# AK4493-Combi8.net
KiCad netlist of a schematic drawn in EAGLE
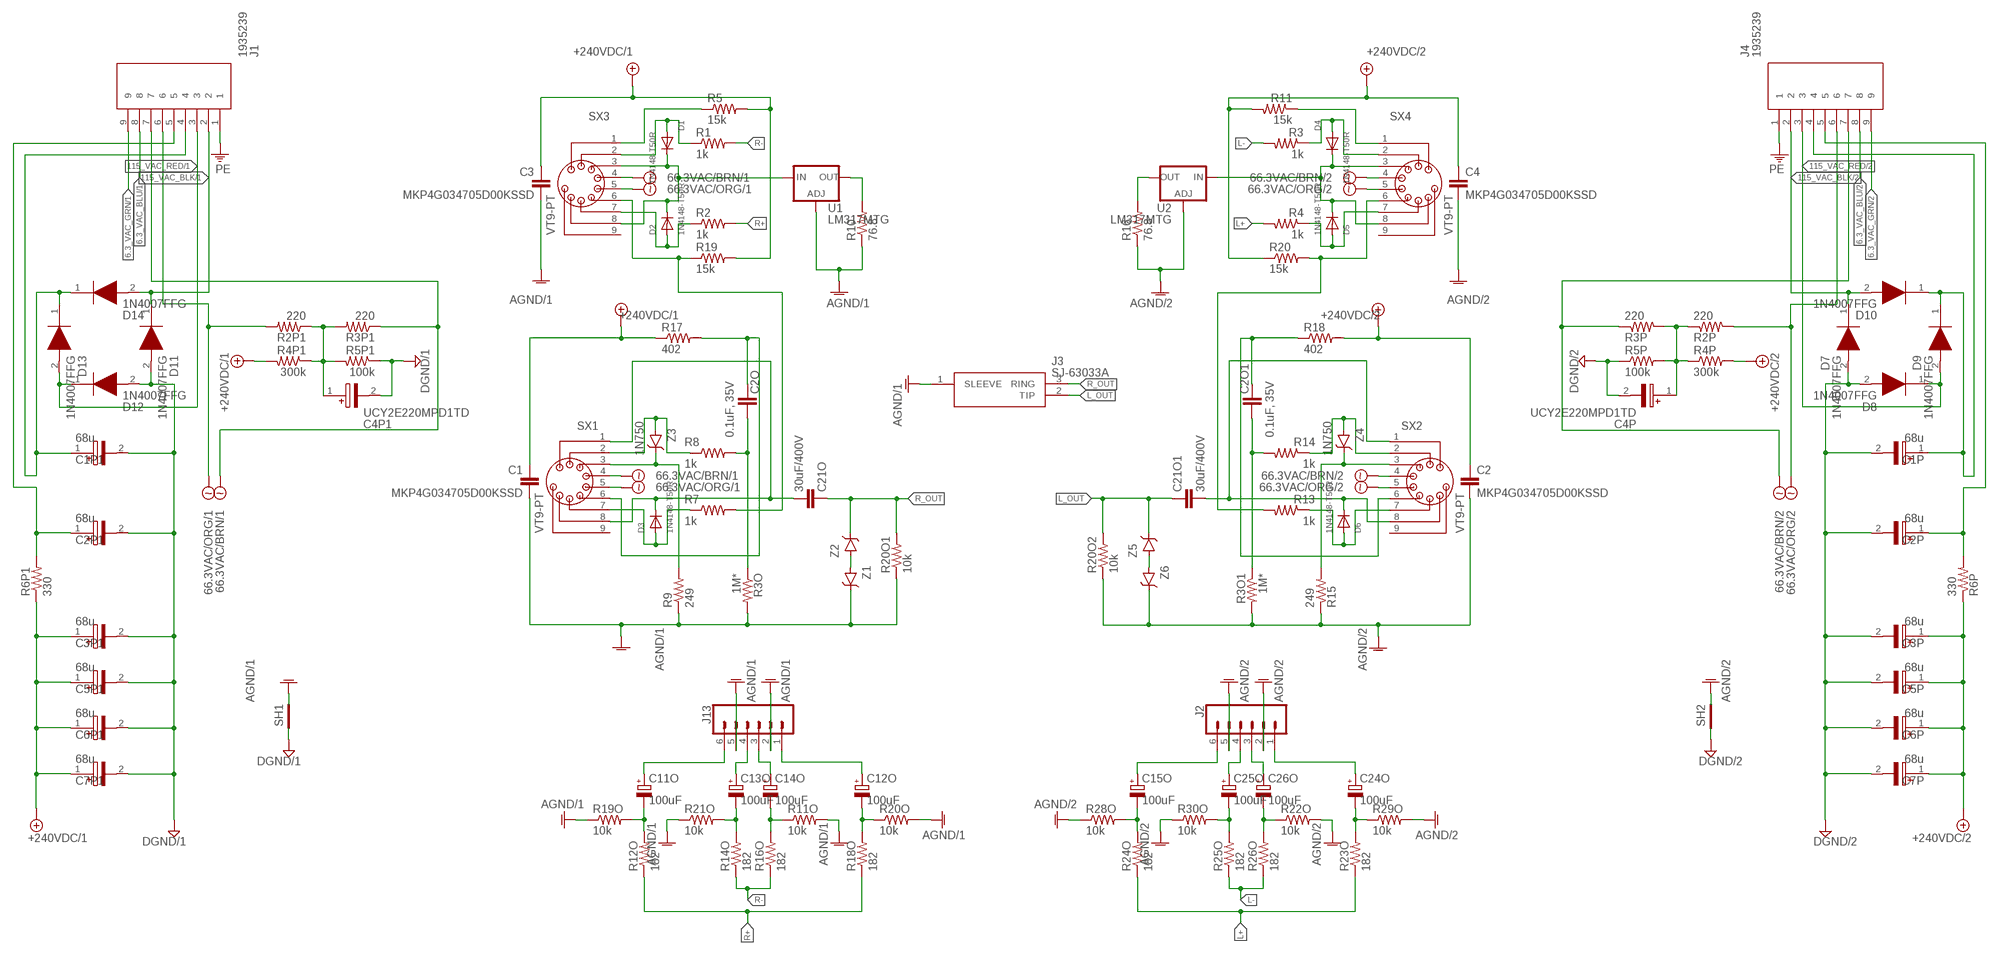
[diagram p0: schematic, sheet 1]

(export (version "E")
  (design (tool "Eeschema 10.0.6"))
  (components
    (comp (ref "C1")
      (value "MKP4G034705D00KSSD")
      (footprint "eagle-import:MKP4G034705D00KSSD")
      (fields (field (name "MOUSER_PART_NUMBER") "505-MKP4G034705DKSSD"))
      (libsource (lib "eagle-import") (part "MKP4G034705D00KSSD"))
    )
    (comp (ref "C1P")
      (value "68u")
      (footprint "eagle-import:CAPPRD750W80D1475H4700")
      (fields (field (name "MANUFACTURER_PART_NUMBER") "500HXW68MEFR14.5X45"))
      (libsource (lib "eagle-import") (part "500HXW68MEFR14.5X45"))
    )
    (comp (ref "C1P1")
      (value "68u")
      (footprint "eagle-import:CAPPRD750W80D1475H4700")
      (fields (field (name "MANUFACTURER_PART_NUMBER") "500HXW68MEFR14.5X45"))
      (libsource (lib "eagle-import") (part "500HXW68MEFR14.5X45"))
    )
    (comp (ref "C2")
      (value "MKP4G034705D00KSSD")
      (footprint "eagle-import:MKP4G034705D00KSSD")
      (fields (field (name "MOUSER_PART_NUMBER") "505-MKP4G034705DKSSD"))
      (libsource (lib "eagle-import") (part "MKP4G034705D00KSSD"))
    )
    (comp (ref "C2O")
      (value "0.1uF, 35V")
      (footprint "eagle-import:MKS4B031002A00JC00")
      (fields
        (field (name "MANUFACTURER_PART_NUMBER") "MKS4B031002A00JC00")
        (field (name "MOUSER_PART_NUMBER") "505-MKS4B0312AJC")
      )
      (libsource (lib "eagle-import") (part "MKS4B031002A00JC00"))
    )
    (comp (ref "C2O1")
      (value "0.1uF, 35V")
      (footprint "eagle-import:MKS4B031002A00JC00")
      (fields
        (field (name "MANUFACTURER_PART_NUMBER") "MKS4B031002A00JC00")
        (field (name "MOUSER_PART_NUMBER") "505-MKS4B0312AJC")
      )
      (libsource (lib "eagle-import") (part "MKS4B031002A00JC00"))
    )
    (comp (ref "C2P")
      (value "68u")
      (footprint "eagle-import:CAPPRD750W80D1475H4700")
      (fields (field (name "MANUFACTURER_PART_NUMBER") "500HXW68MEFR14.5X45"))
      (libsource (lib "eagle-import") (part "500HXW68MEFR14.5X45"))
    )
    (comp (ref "C2P1")
      (value "68u")
      (footprint "eagle-import:CAPPRD750W80D1475H4700")
      (fields (field (name "MANUFACTURER_PART_NUMBER") "500HXW68MEFR14.5X45"))
      (libsource (lib "eagle-import") (part "500HXW68MEFR14.5X45"))
    )
    (comp (ref "C3")
      (value "MKP4G034705D00KSSD")
      (footprint "eagle-import:MKP4G034705D00KSSD")
      (fields (field (name "MOUSER_PART_NUMBER") "505-MKP4G034705DKSSD"))
      (libsource (lib "eagle-import") (part "MKP4G034705D00KSSD"))
    )
    (comp (ref "C3P")
      (value "68u")
      (footprint "eagle-import:CAPPRD750W80D1475H4700")
      (fields (field (name "MANUFACTURER_PART_NUMBER") "500HXW68MEFR14.5X45"))
      (libsource (lib "eagle-import") (part "500HXW68MEFR14.5X45"))
    )
    (comp (ref "C3P1")
      (value "68u")
      (footprint "eagle-import:CAPPRD750W80D1475H4700")
      (fields (field (name "MANUFACTURER_PART_NUMBER") "500HXW68MEFR14.5X45"))
      (libsource (lib "eagle-import") (part "500HXW68MEFR14.5X45"))
    )
    (comp (ref "C4")
      (value "MKP4G034705D00KSSD")
      (footprint "eagle-import:MKP4G034705D00KSSD")
      (fields (field (name "MOUSER_PART_NUMBER") "505-MKP4G034705DKSSD"))
      (libsource (lib "eagle-import") (part "MKP4G034705D00KSSD"))
    )
    (comp (ref "C4P")
      (value "UCY2E220MPD1TD")
      (footprint "eagle-import:CAPPRD500W60D1025H1750")
      (fields (field (name "MOUSER_PART_NUMBER") "647-UCY2E220MPD1TD"))
      (libsource (lib "eagle-import") (part "UCY2E220MPD1TD"))
    )
    (comp (ref "C4P1")
      (value "UCY2E220MPD1TD")
      (footprint "eagle-import:CAPPRD500W60D1025H1750")
      (fields (field (name "MOUSER_PART_NUMBER") "647-UCY2E220MPD1TD"))
      (libsource (lib "eagle-import") (part "UCY2E220MPD1TD"))
    )
    (comp (ref "C5P")
      (value "68u")
      (footprint "eagle-import:CAPPRD750W80D1475H4700")
      (fields (field (name "MANUFACTURER_PART_NUMBER") "500HXW68MEFR14.5X45"))
      (libsource (lib "eagle-import") (part "500HXW68MEFR14.5X45"))
    )
    (comp (ref "C5P1")
      (value "68u")
      (footprint "eagle-import:CAPPRD750W80D1475H4700")
      (fields (field (name "MANUFACTURER_PART_NUMBER") "500HXW68MEFR14.5X45"))
      (libsource (lib "eagle-import") (part "500HXW68MEFR14.5X45"))
    )
    (comp (ref "C6P")
      (value "68u")
      (footprint "eagle-import:CAPPRD750W80D1475H4700")
      (fields (field (name "MANUFACTURER_PART_NUMBER") "500HXW68MEFR14.5X45"))
      (libsource (lib "eagle-import") (part "500HXW68MEFR14.5X45"))
    )
    (comp (ref "C6P1")
      (value "68u")
      (footprint "eagle-import:CAPPRD750W80D1475H4700")
      (fields (field (name "MANUFACTURER_PART_NUMBER") "500HXW68MEFR14.5X45"))
      (libsource (lib "eagle-import") (part "500HXW68MEFR14.5X45"))
    )
    (comp (ref "C7P")
      (value "68u")
      (footprint "eagle-import:CAPPRD750W80D1475H4700")
      (fields (field (name "MANUFACTURER_PART_NUMBER") "500HXW68MEFR14.5X45"))
      (libsource (lib "eagle-import") (part "500HXW68MEFR14.5X45"))
    )
    (comp (ref "C7P1")
      (value "68u")
      (footprint "eagle-import:CAPPRD750W80D1475H4700")
      (fields (field (name "MANUFACTURER_PART_NUMBER") "500HXW68MEFR14.5X45"))
      (libsource (lib "eagle-import") (part "500HXW68MEFR14.5X45"))
    )
    (comp (ref "C11O")
      (value "100uF")
      (footprint "eagle-import:CAPPRD350W60D825H1300")
      (fields
        (field (name "ARROW_PART_NUMBER") "UFW1H101MPD1TD")
        (field (name "MOUSER_PART_NUMBER") "647-UFW1H101MPD1TD")
      )
      (libsource (lib "eagle-import") (part "UFW1H101MPD1TD"))
    )
    (comp (ref "C12O")
      (value "100uF")
      (footprint "eagle-import:CAPPRD350W60D825H1300")
      (fields
        (field (name "ARROW_PART_NUMBER") "UFW1H101MPD1TD")
        (field (name "MOUSER_PART_NUMBER") "647-UFW1H101MPD1TD")
      )
      (libsource (lib "eagle-import") (part "UFW1H101MPD1TD"))
    )
    (comp (ref "C13O")
      (value "100uF")
      (footprint "eagle-import:CAPPRD350W60D825H1300")
      (fields
        (field (name "ARROW_PART_NUMBER") "UFW1H101MPD1TD")
        (field (name "MOUSER_PART_NUMBER") "647-UFW1H101MPD1TD")
      )
      (libsource (lib "eagle-import") (part "UFW1H101MPD1TD"))
    )
    (comp (ref "C14O")
      (value "100uF")
      (footprint "eagle-import:CAPPRD350W60D825H1300")
      (fields
        (field (name "ARROW_PART_NUMBER") "UFW1H101MPD1TD")
        (field (name "MOUSER_PART_NUMBER") "647-UFW1H101MPD1TD")
      )
      (libsource (lib "eagle-import") (part "UFW1H101MPD1TD"))
    )
    (comp (ref "C15O")
      (value "100uF")
      (footprint "eagle-import:CAPPRD350W60D825H1300")
      (fields
        (field (name "ARROW_PART_NUMBER") "UFW1H101MPD1TD")
        (field (name "MOUSER_PART_NUMBER") "647-UFW1H101MPD1TD")
      )
      (libsource (lib "eagle-import") (part "UFW1H101MPD1TD"))
    )
    (comp (ref "C21O")
      (value "30uF/400V")
      (footprint "eagle-import:DCP4G056007GD4KSSD")
      (fields
        (field (name "MANUFACTURER_PART_NUMBER") "DCP4G056007GD4KSSD")
        (field (name "MOUSER_PART_NUMBER") "505-DCP4G056007GD4KS")
      )
      (libsource (lib "eagle-import") (part "DCP4G056007GD4KSSD"))
    )
    (comp (ref "C21O1")
      (value "30uF/400V")
      (footprint "eagle-import:DCP4G056007GD4KSSD")
      (fields
        (field (name "MANUFACTURER_PART_NUMBER") "DCP4G056007GD4KSSD")
        (field (name "MOUSER_PART_NUMBER") "505-DCP4G056007GD4KS")
      )
      (libsource (lib "eagle-import") (part "DCP4G056007GD4KSSD"))
    )
    (comp (ref "C24O")
      (value "100uF")
      (footprint "eagle-import:CAPPRD350W60D825H1300")
      (fields
        (field (name "ARROW_PART_NUMBER") "UFW1H101MPD1TD")
        (field (name "MOUSER_PART_NUMBER") "647-UFW1H101MPD1TD")
      )
      (libsource (lib "eagle-import") (part "UFW1H101MPD1TD"))
    )
    (comp (ref "C25O")
      (value "100uF")
      (footprint "eagle-import:CAPPRD350W60D825H1300")
      (fields
        (field (name "ARROW_PART_NUMBER") "UFW1H101MPD1TD")
        (field (name "MOUSER_PART_NUMBER") "647-UFW1H101MPD1TD")
      )
      (libsource (lib "eagle-import") (part "UFW1H101MPD1TD"))
    )
    (comp (ref "C26O")
      (value "100uF")
      (footprint "eagle-import:CAPPRD350W60D825H1300")
      (fields
        (field (name "ARROW_PART_NUMBER") "UFW1H101MPD1TD")
        (field (name "MOUSER_PART_NUMBER") "647-UFW1H101MPD1TD")
      )
      (libsource (lib "eagle-import") (part "UFW1H101MPD1TD"))
    )
    (comp (ref "D1")
      (value "1N4148-T50R")
      (footprint "eagle-import:DIOAD1068W53L380D172")
      (fields (field (name "MOUSER_PART_NUMBER") "512-1N4148T50R"))
      (libsource (lib "eagle-import") (part "1N4148-T50R"))
    )
    (comp (ref "D2")
      (value "1N4148-T50R")
      (footprint "eagle-import:DIOAD1068W53L380D172")
      (fields (field (name "MOUSER_PART_NUMBER") "512-1N4148T50R"))
      (libsource (lib "eagle-import") (part "1N4148-T50R"))
    )
    (comp (ref "D3")
      (value "1N4148-T50R")
      (footprint "eagle-import:DIOAD1068W53L380D172")
      (fields (field (name "MOUSER_PART_NUMBER") "512-1N4148T50R"))
      (libsource (lib "eagle-import") (part "1N4148-T50R"))
    )
    (comp (ref "D4")
      (value "1N4148-T50R")
      (footprint "eagle-import:DIOAD1068W53L380D172")
      (fields (field (name "MOUSER_PART_NUMBER") "512-1N4148T50R"))
      (libsource (lib "eagle-import") (part "1N4148-T50R"))
    )
    (comp (ref "D5")
      (value "1N4148-T50R")
      (footprint "eagle-import:DIOAD1068W53L380D172")
      (fields (field (name "MOUSER_PART_NUMBER") "512-1N4148T50R"))
      (libsource (lib "eagle-import") (part "1N4148-T50R"))
    )
    (comp (ref "D6")
      (value "1N4148-T50R")
      (footprint "eagle-import:DIOAD1068W53L380D172")
      (fields (field (name "MOUSER_PART_NUMBER") "512-1N4148T50R"))
      (libsource (lib "eagle-import") (part "1N4148-T50R"))
    )
    (comp (ref "D7")
      (value "1N4007FFG")
      (footprint "eagle-import:DIOAD1405W86L465D235")
      (fields (field (name "MOUSER_PART_NUMBER") "863-1N4007FFG"))
      (libsource (lib "eagle-import") (part "1N4007FFG"))
    )
    (comp (ref "D8")
      (value "1N4007FFG")
      (footprint "eagle-import:DIOAD1405W86L465D235")
      (fields (field (name "MOUSER_PART_NUMBER") "863-1N4007FFG"))
      (libsource (lib "eagle-import") (part "1N4007FFG"))
    )
    (comp (ref "D9")
      (value "1N4007FFG")
      (footprint "eagle-import:DIOAD1405W86L465D235")
      (fields (field (name "MOUSER_PART_NUMBER") "863-1N4007FFG"))
      (libsource (lib "eagle-import") (part "1N4007FFG"))
    )
    (comp (ref "D10")
      (value "1N4007FFG")
      (footprint "eagle-import:DIOAD1405W86L465D235")
      (fields (field (name "MOUSER_PART_NUMBER") "863-1N4007FFG"))
      (libsource (lib "eagle-import") (part "1N4007FFG"))
    )
    (comp (ref "D11")
      (value "1N4007FFG")
      (footprint "eagle-import:DIOAD1405W86L465D235")
      (fields (field (name "MOUSER_PART_NUMBER") "863-1N4007FFG"))
      (libsource (lib "eagle-import") (part "1N4007FFG"))
    )
    (comp (ref "D12")
      (value "1N4007FFG")
      (footprint "eagle-import:DIOAD1405W86L465D235")
      (fields (field (name "MOUSER_PART_NUMBER") "863-1N4007FFG"))
      (libsource (lib "eagle-import") (part "1N4007FFG"))
    )
    (comp (ref "D13")
      (value "1N4007FFG")
      (footprint "eagle-import:DIOAD1405W86L465D235")
      (fields (field (name "MOUSER_PART_NUMBER") "863-1N4007FFG"))
      (libsource (lib "eagle-import") (part "1N4007FFG"))
    )
    (comp (ref "D14")
      (value "1N4007FFG")
      (footprint "eagle-import:DIOAD1405W86L465D235")
      (fields (field (name "MOUSER_PART_NUMBER") "863-1N4007FFG"))
      (libsource (lib "eagle-import") (part "1N4007FFG"))
    )
    (comp (ref "J1")
      (value "1935239")
      (footprint "eagle-import:1935239")
      (fields (field (name "MOUSER_PART_NUMBER") "651-1935239"))
      (libsource (lib "eagle-import") (part "1935239"))
    )
    (comp (ref "J2")
      (value "CONN_06SILK_FEMALE_PTH")
      (footprint "eagle-import:1X06")
      (libsource (lib "eagle-import") (part "CONN_06SILK_FEMALE_PTH"))
    )
    (comp (ref "J3")
      (value "SJ-63033A")
      (footprint "eagle-import:SJ63033A")
      (libsource (lib "eagle-import") (part "SJ-63033A"))
    )
    (comp (ref "J4")
      (value "1935239")
      (footprint "eagle-import:1935239")
      (fields (field (name "MOUSER_PART_NUMBER") "651-1935239"))
      (libsource (lib "eagle-import") (part "1935239"))
    )
    (comp (ref "J13")
      (value "CONN_06SILK_FEMALE_PTH")
      (footprint "eagle-import:1X06")
      (libsource (lib "eagle-import") (part "CONN_06SILK_FEMALE_PTH"))
    )
    (comp (ref "R1")
      (value "1k")
      (footprint "eagle-import:0207_10")
      (fields
        (field (name "MANUFACTURER_PART_NUMBER") "LR1F1K0")
        (field (name "MOUSER_PART_NUMBER") "279-LR1F1K0")
      )
      (libsource (lib "eagle-import") (part "LR1F1K0"))
    )
    (comp (ref "R2")
      (value "1k")
      (footprint "eagle-import:0207_10")
      (fields
        (field (name "MANUFACTURER_PART_NUMBER") "LR1F1K0")
        (field (name "MOUSER_PART_NUMBER") "279-LR1F1K0")
      )
      (libsource (lib "eagle-import") (part "LR1F1K0"))
    )
    (comp (ref "R2P")
      (value "220")
      (footprint "eagle-import:0411_15")
      (libsource (lib "eagle-import") (part "R-US_0411/15"))
    )
    (comp (ref "R2P1")
      (value "220")
      (footprint "eagle-import:0411_15")
      (libsource (lib "eagle-import") (part "R-US_0411/15"))
    )
    (comp (ref "R3")
      (value "1k")
      (footprint "eagle-import:0207_10")
      (fields
        (field (name "MANUFACTURER_PART_NUMBER") "LR1F1K0")
        (field (name "MOUSER_PART_NUMBER") "279-LR1F1K0")
      )
      (libsource (lib "eagle-import") (part "LR1F1K0"))
    )
    (comp (ref "R3O")
      (value "1M*")
      (footprint "eagle-import:0207_10")
      (fields
        (field (name "MANUFACTURER_PART_NUMBER") "LR1F1M0")
        (field (name "MOUSER_PART_NUMBER") "279-LR1F1M0")
      )
      (libsource (lib "eagle-import") (part "LR1F1M0"))
    )
    (comp (ref "R3O1")
      (value "1M*")
      (footprint "eagle-import:0207_10")
      (fields
        (field (name "MANUFACTURER_PART_NUMBER") "LR1F1M0")
        (field (name "MOUSER_PART_NUMBER") "279-LR1F1M0")
      )
      (libsource (lib "eagle-import") (part "LR1F1M0"))
    )
    (comp (ref "R3P")
      (value "220")
      (footprint "eagle-import:0411_15")
      (libsource (lib "eagle-import") (part "R-US_0411/15"))
    )
    (comp (ref "R3P1")
      (value "220")
      (footprint "eagle-import:0411_15")
      (libsource (lib "eagle-import") (part "R-US_0411/15"))
    )
    (comp (ref "R4")
      (value "1k")
      (footprint "eagle-import:0207_10")
      (fields
        (field (name "MANUFACTURER_PART_NUMBER") "LR1F1K0")
        (field (name "MOUSER_PART_NUMBER") "279-LR1F1K0")
      )
      (libsource (lib "eagle-import") (part "LR1F1K0"))
    )
    (comp (ref "R4P")
      (value "300k")
      (footprint "eagle-import:0411_15")
      (libsource (lib "eagle-import") (part "R-US_0411/15"))
    )
    (comp (ref "R4P1")
      (value "300k")
      (footprint "eagle-import:0411_15")
      (libsource (lib "eagle-import") (part "R-US_0411/15"))
    )
    (comp (ref "R5")
      (value "15k")
      (footprint "eagle-import:0411_15")
      (fields
        (field (name "MANUFACTURER_PART_NUMBER") "CPF215K000FKE14")
        (field (name "MOUSER_PART_NUMBER") "71-CPF2-F-15K-E3")
      )
      (libsource (lib "eagle-import") (part "CPF215K000FKE14"))
    )
    (comp (ref "R5P")
      (value "100k")
      (footprint "eagle-import:0411_15")
      (libsource (lib "eagle-import") (part "R-US_0411/15"))
    )
    (comp (ref "R5P1")
      (value "100k")
      (footprint "eagle-import:0411_15")
      (libsource (lib "eagle-import") (part "R-US_0411/15"))
    )
    (comp (ref "R6P")
      (value "330")
      (footprint "eagle-import:0411_15")
      (libsource (lib "eagle-import") (part "R-US_0411/15"))
    )
    (comp (ref "R6P1")
      (value "330")
      (footprint "eagle-import:0411_15")
      (libsource (lib "eagle-import") (part "R-US_0411/15"))
    )
    (comp (ref "R7")
      (value "1k")
      (footprint "eagle-import:0207_10")
      (fields
        (field (name "MANUFACTURER_PART_NUMBER") "LR1F1K0")
        (field (name "MOUSER_PART_NUMBER") "279-LR1F1K0")
      )
      (libsource (lib "eagle-import") (part "LR1F1K0"))
    )
    (comp (ref "R8")
      (value "1k")
      (footprint "eagle-import:0207_10")
      (fields
        (field (name "MANUFACTURER_PART_NUMBER") "LR1F1K0")
        (field (name "MOUSER_PART_NUMBER") "279-LR1F1K0")
      )
      (libsource (lib "eagle-import") (part "LR1F1K0"))
    )
    (comp (ref "R9")
      (value "249")
      (footprint "eagle-import:0207_10")
      (fields (field (name "MANUFACTURER_PART_NUMBER") "MBB02070C2490FRP00"))
      (libsource (lib "eagle-import") (part "MBB02070C2490FRP00"))
    )
    (comp (ref "R10")
      (value "76.8")
      (footprint "eagle-import:0207_10")
      (fields (field (name "MANUFACTURER_PART_NUMBER") "YR1B76R8CC"))
      (libsource (lib "eagle-import") (part "YR1B76R8CC"))
    )
    (comp (ref "R11")
      (value "15k")
      (footprint "eagle-import:0411_15")
      (fields
        (field (name "MANUFACTURER_PART_NUMBER") "CPF215K000FKE14")
        (field (name "MOUSER_PART_NUMBER") "71-CPF2-F-15K-E3")
      )
      (libsource (lib "eagle-import") (part "CPF215K000FKE14"))
    )
    (comp (ref "R11O")
      (value "10k")
      (footprint "eagle-import:0207_10")
      (fields
        (field (name "MANUFACTURER_PART_NUMBER") "LR1F10K")
        (field (name "MOUSER_PART_NUMBER") "279-LR1F10K")
      )
      (libsource (lib "eagle-import") (part "LR1F10K"))
    )
    (comp (ref "R12O")
      (value "182")
      (footprint "eagle-import:0207_10")
      (fields
        (field (name "MANUFACTURER") "Yageo")
        (field (name "MANUFACTURER_PART_NUMBER") "MF0207FTE52-182R")
        (field (name "MOUSER_PART_NUMBER") "603-MF0207FTE52-182R")
      )
      (libsource (lib "eagle-import") (part "MF0207FTE52-182R"))
    )
    (comp (ref "R13")
      (value "1k")
      (footprint "eagle-import:0207_10")
      (fields
        (field (name "MANUFACTURER_PART_NUMBER") "LR1F1K0")
        (field (name "MOUSER_PART_NUMBER") "279-LR1F1K0")
      )
      (libsource (lib "eagle-import") (part "LR1F1K0"))
    )
    (comp (ref "R14")
      (value "1k")
      (footprint "eagle-import:0207_10")
      (fields
        (field (name "MANUFACTURER_PART_NUMBER") "LR1F1K0")
        (field (name "MOUSER_PART_NUMBER") "279-LR1F1K0")
      )
      (libsource (lib "eagle-import") (part "LR1F1K0"))
    )
    (comp (ref "R14O")
      (value "182")
      (footprint "eagle-import:0207_10")
      (fields
        (field (name "MANUFACTURER") "Yageo")
        (field (name "MANUFACTURER_PART_NUMBER") "MF0207FTE52-182R")
        (field (name "MOUSER_PART_NUMBER") "603-MF0207FTE52-182R")
      )
      (libsource (lib "eagle-import") (part "MF0207FTE52-182R"))
    )
    (comp (ref "R15")
      (value "249")
      (footprint "eagle-import:0207_10")
      (fields (field (name "MANUFACTURER_PART_NUMBER") "MBB02070C2490FRP00"))
      (libsource (lib "eagle-import") (part "MBB02070C2490FRP00"))
    )
    (comp (ref "R16")
      (value "76.8")
      (footprint "eagle-import:0207_10")
      (fields (field (name "MANUFACTURER_PART_NUMBER") "YR1B76R8CC"))
      (libsource (lib "eagle-import") (part "YR1B76R8CC"))
    )
    (comp (ref "R16O")
      (value "182")
      (footprint "eagle-import:0207_10")
      (fields
        (field (name "MANUFACTURER") "Yageo")
        (field (name "MANUFACTURER_PART_NUMBER") "MF0207FTE52-182R")
        (field (name "MOUSER_PART_NUMBER") "603-MF0207FTE52-182R")
      )
      (libsource (lib "eagle-import") (part "MF0207FTE52-182R"))
    )
    (comp (ref "R17")
      (value "402")
      (footprint "eagle-import:0617_22")
      (fields (field (name "MANUFACTURER_PART_NUMBER") "RWR80S4020FRB12"))
      (libsource (lib "eagle-import") (part "RWR80S4020FRB12"))
    )
    (comp (ref "R18")
      (value "402")
      (footprint "eagle-import:0617_22")
      (fields (field (name "MANUFACTURER_PART_NUMBER") "RWR80S4020FRB12"))
      (libsource (lib "eagle-import") (part "RWR80S4020FRB12"))
    )
    (comp (ref "R18O")
      (value "182")
      (footprint "eagle-import:0207_10")
      (fields
        (field (name "MANUFACTURER") "Yageo")
        (field (name "MANUFACTURER_PART_NUMBER") "MF0207FTE52-182R")
        (field (name "MOUSER_PART_NUMBER") "603-MF0207FTE52-182R")
      )
      (libsource (lib "eagle-import") (part "MF0207FTE52-182R"))
    )
    (comp (ref "R19")
      (value "15k")
      (footprint "eagle-import:0411_15")
      (fields
        (field (name "MANUFACTURER_PART_NUMBER") "CPF215K000FKE14")
        (field (name "MOUSER_PART_NUMBER") "71-CPF2-F-15K-E3")
      )
      (libsource (lib "eagle-import") (part "CPF215K000FKE14"))
    )
    (comp (ref "R19O")
      (value "10k")
      (footprint "eagle-import:0207_10")
      (fields
        (field (name "MANUFACTURER_PART_NUMBER") "LR1F10K")
        (field (name "MOUSER_PART_NUMBER") "279-LR1F10K")
      )
      (libsource (lib "eagle-import") (part "LR1F10K"))
    )
    (comp (ref "R20")
      (value "15k")
      (footprint "eagle-import:0411_15")
      (fields
        (field (name "MANUFACTURER_PART_NUMBER") "CPF215K000FKE14")
        (field (name "MOUSER_PART_NUMBER") "71-CPF2-F-15K-E3")
      )
      (libsource (lib "eagle-import") (part "CPF215K000FKE14"))
    )
    (comp (ref "R20O")
      (value "10k")
      (footprint "eagle-import:0207_10")
      (fields
        (field (name "MANUFACTURER_PART_NUMBER") "LR1F10K")
        (field (name "MOUSER_PART_NUMBER") "279-LR1F10K")
      )
      (libsource (lib "eagle-import") (part "LR1F10K"))
    )
    (comp (ref "R20O1")
      (value "10k")
      (footprint "eagle-import:0207_10")
      (fields
        (field (name "MANUFACTURER_PART_NUMBER") "LR1F10K")
        (field (name "MOUSER_PART_NUMBER") "279-LR1F10K")
      )
      (libsource (lib "eagle-import") (part "LR1F10K"))
    )
    (comp (ref "R20O2")
      (value "10k")
      (footprint "eagle-import:0207_10")
      (fields
        (field (name "MANUFACTURER_PART_NUMBER") "LR1F10K")
        (field (name "MOUSER_PART_NUMBER") "279-LR1F10K")
      )
      (libsource (lib "eagle-import") (part "LR1F10K"))
    )
    (comp (ref "R21O")
      (value "10k")
      (footprint "eagle-import:0207_10")
      (fields
        (field (name "MANUFACTURER_PART_NUMBER") "LR1F10K")
        (field (name "MOUSER_PART_NUMBER") "279-LR1F10K")
      )
      (libsource (lib "eagle-import") (part "LR1F10K"))
    )
    (comp (ref "R22O")
      (value "10k")
      (footprint "eagle-import:0207_10")
      (fields
        (field (name "MANUFACTURER_PART_NUMBER") "LR1F10K")
        (field (name "MOUSER_PART_NUMBER") "279-LR1F10K")
      )
      (libsource (lib "eagle-import") (part "LR1F10K"))
    )
    (comp (ref "R23O")
      (value "182")
      (footprint "eagle-import:0207_10")
      (fields
        (field (name "MANUFACTURER") "Yageo")
        (field (name "MANUFACTURER_PART_NUMBER") "MF0207FTE52-182R")
        (field (name "MOUSER_PART_NUMBER") "603-MF0207FTE52-182R")
      )
      (libsource (lib "eagle-import") (part "MF0207FTE52-182R"))
    )
    (comp (ref "R24O")
      (value "182")
      (footprint "eagle-import:0207_10")
      (fields
        (field (name "MANUFACTURER") "Yageo")
        (field (name "MANUFACTURER_PART_NUMBER") "MF0207FTE52-182R")
        (field (name "MOUSER_PART_NUMBER") "603-MF0207FTE52-182R")
      )
      (libsource (lib "eagle-import") (part "MF0207FTE52-182R"))
    )
    (comp (ref "R25O")
      (value "182")
      (footprint "eagle-import:0207_10")
      (fields
        (field (name "MANUFACTURER") "Yageo")
        (field (name "MANUFACTURER_PART_NUMBER") "MF0207FTE52-182R")
        (field (name "MOUSER_PART_NUMBER") "603-MF0207FTE52-182R")
      )
      (libsource (lib "eagle-import") (part "MF0207FTE52-182R"))
    )
    (comp (ref "R26O")
      (value "182")
      (footprint "eagle-import:0207_10")
      (fields
        (field (name "MANUFACTURER") "Yageo")
        (field (name "MANUFACTURER_PART_NUMBER") "MF0207FTE52-182R")
        (field (name "MOUSER_PART_NUMBER") "603-MF0207FTE52-182R")
      )
      (libsource (lib "eagle-import") (part "MF0207FTE52-182R"))
    )
    (comp (ref "R28O")
      (value "10k")
      (footprint "eagle-import:0207_10")
      (fields
        (field (name "MANUFACTURER_PART_NUMBER") "LR1F10K")
        (field (name "MOUSER_PART_NUMBER") "279-LR1F10K")
      )
      (libsource (lib "eagle-import") (part "LR1F10K"))
    )
    (comp (ref "R29O")
      (value "10k")
      (footprint "eagle-import:0207_10")
      (fields
        (field (name "MANUFACTURER_PART_NUMBER") "LR1F10K")
        (field (name "MOUSER_PART_NUMBER") "279-LR1F10K")
      )
      (libsource (lib "eagle-import") (part "LR1F10K"))
    )
    (comp (ref "R30O")
      (value "10k")
      (footprint "eagle-import:0207_10")
      (fields
        (field (name "MANUFACTURER_PART_NUMBER") "LR1F10K")
        (field (name "MOUSER_PART_NUMBER") "279-LR1F10K")
      )
      (libsource (lib "eagle-import") (part "LR1F10K"))
    )
    (comp (ref "SH1")
      (value "SHORTA5")
      (footprint "eagle-import:SHORT_ALL-50")
      (libsource (lib "eagle-import") (part "SHORTA5"))
    )
    (comp (ref "SH2")
      (value "SHORTA5")
      (footprint "eagle-import:SHORT_ALL-50")
      (libsource (lib "eagle-import") (part "SHORTA5"))
    )
    (comp (ref "SX1")
      (value "VT9-PT")
      (footprint "eagle-import:VT9-PT")
      (libsource (lib "eagle-import") (part "VT9-PT"))
    )
    (comp (ref "SX2")
      (value "VT9-PT")
      (footprint "eagle-import:VT9-PT")
      (libsource (lib "eagle-import") (part "VT9-PT"))
    )
    (comp (ref "SX3")
      (value "VT9-PT")
      (footprint "eagle-import:VT9-PT")
      (libsource (lib "eagle-import") (part "VT9-PT"))
    )
    (comp (ref "SX4")
      (value "VT9-PT")
      (footprint "eagle-import:VT9-PT")
      (libsource (lib "eagle-import") (part "VT9-PT"))
    )
    (comp (ref "U1")
      (value "LM317MTG")
      (footprint "eagle-import:TO254P482X997X2018-3P")
      (fields (field (name "MOUSER_PART_NUMBER") "863-LM317MTG"))
      (libsource (lib "eagle-import") (part "LM317MTG"))
    )
    (comp (ref "U2")
      (value "LM317MTG")
      (footprint "eagle-import:TO254P482X997X2018-3P")
      (fields (field (name "MOUSER_PART_NUMBER") "863-LM317MTG"))
      (libsource (lib "eagle-import") (part "LM317MTG"))
    )
    (comp (ref "Z1")
      (value "BZX79-C16,113")
      (footprint "eagle-import:DIOAD1165W56L425D185")
      (libsource (lib "eagle-import") (part "BZX79-C16,113"))
    )
    (comp (ref "Z2")
      (value "BZX79-C16,113")
      (footprint "eagle-import:DIOAD1165W56L425D185")
      (libsource (lib "eagle-import") (part "BZX79-C16,113"))
    )
    (comp (ref "Z3")
      (value "1N750")
      (footprint "eagle-import:DIOAD1256W56L444D203")
      (fields (field (name "MOUSER_PART_NUMBER") "494-1N750(DO-35)"))
      (libsource (lib "eagle-import") (part "1N750"))
    )
    (comp (ref "Z4")
      (value "1N750")
      (footprint "eagle-import:DIOAD1256W56L444D203")
      (fields (field (name "MOUSER_PART_NUMBER") "494-1N750(DO-35)"))
      (libsource (lib "eagle-import") (part "1N750"))
    )
    (comp (ref "Z5")
      (value "BZX79-C16,113")
      (footprint "eagle-import:DIOAD1165W56L425D185")
      (libsource (lib "eagle-import") (part "BZX79-C16,113"))
    )
    (comp (ref "Z6")
      (value "BZX79-C16,113")
      (footprint "eagle-import:DIOAD1165W56L425D185")
      (libsource (lib "eagle-import") (part "BZX79-C16,113"))
    )
  )
  (nets
    (net (code "1") (name "+240VDC{slash}1") (class "Default")
      (node (ref "C1") (pin "1") (pinfunction "1_1") (pintype "passive"))
      (node (ref "C3") (pin "1") (pinfunction "1_1") (pintype "passive"))
      (node (ref "C3P1") (pin "1") (pinfunction "+_1") (pintype "bidirectional"))
      (node (ref "C5P1") (pin "1") (pinfunction "+_1") (pintype "bidirectional"))
      (node (ref "C6P1") (pin "1") (pinfunction "+_1") (pintype "bidirectional"))
      (node (ref "C7P1") (pin "1") (pinfunction "+_1") (pintype "bidirectional"))
      (node (ref "R17") (pin "1") (pinfunction "1_1") (pintype "passive"))
      (node (ref "R19") (pin "2") (pinfunction "2_2") (pintype "passive"))
      (node (ref "R4P1") (pin "2") (pinfunction "2_2") (pintype "passive"))
      (node (ref "R5") (pin "2") (pinfunction "2_2") (pintype "passive"))
      (node (ref "R6P1") (pin "1") (pinfunction "1_1") (pintype "passive"))
    )
    (net (code "2") (name "+240VDC{slash}2") (class "Default")
      (node (ref "C2") (pin "1") (pinfunction "1_1") (pintype "passive"))
      (node (ref "C3P") (pin "1") (pinfunction "+_1") (pintype "bidirectional"))
      (node (ref "C4") (pin "1") (pinfunction "1_1") (pintype "passive"))
      (node (ref "C5P") (pin "1") (pinfunction "+_1") (pintype "bidirectional"))
      (node (ref "C6P") (pin "1") (pinfunction "+_1") (pintype "bidirectional"))
      (node (ref "C7P") (pin "1") (pinfunction "+_1") (pintype "bidirectional"))
      (node (ref "R11") (pin "2") (pinfunction "2_2") (pintype "passive"))
      (node (ref "R18") (pin "2") (pinfunction "2_2") (pintype "passive"))
      (node (ref "R20") (pin "1") (pinfunction "1_1") (pintype "passive"))
      (node (ref "R4P") (pin "2") (pinfunction "2_2") (pintype "passive"))
      (node (ref "R6P") (pin "1") (pinfunction "1_1") (pintype "passive"))
    )
    (net (code "3") (name "6.3_VAC_BLU{slash}1") (class "Default")
      (node (ref "J1") (pin "8") (pinfunction "8_8") (pintype "bidirectional"))
    )
    (net (code "4") (name "6.3_VAC_BLU{slash}2") (class "Default")
      (node (ref "J4") (pin "8") (pinfunction "8_8") (pintype "bidirectional"))
    )
    (net (code "5") (name "6.3_VAC_GRN{slash}1") (class "Default")
      (node (ref "J1") (pin "9") (pinfunction "9_9") (pintype "bidirectional"))
    )
    (net (code "6") (name "6.3_VAC_GRN{slash}2") (class "Default")
      (node (ref "J4") (pin "9") (pinfunction "9_9") (pintype "bidirectional"))
    )
    (net (code "7") (name "66.3VAC{slash}BRN{slash}1") (class "Default")
      (node (ref "J1") (pin "7") (pinfunction "7_7") (pintype "bidirectional"))
      (node (ref "R3P1") (pin "1") (pinfunction "1_1") (pintype "passive"))
      (node (ref "SX1") (pin "4") (pinfunction "4_4") (pintype "passive"))
      (node (ref "SX3") (pin "4") (pinfunction "4_4") (pintype "passive"))
    )
    (net (code "8") (name "66.3VAC{slash}BRN{slash}2") (class "Default")
      (node (ref "J4") (pin "7") (pinfunction "7_7") (pintype "bidirectional"))
      (node (ref "R3P") (pin "1") (pinfunction "1_1") (pintype "passive"))
      (node (ref "SX2") (pin "4") (pinfunction "4_4") (pintype "passive"))
      (node (ref "SX4") (pin "4") (pinfunction "4_4") (pintype "passive"))
    )
    (net (code "9") (name "66.3VAC{slash}ORG{slash}1") (class "Default")
      (node (ref "J1") (pin "6") (pinfunction "6_6") (pintype "bidirectional"))
      (node (ref "R2P1") (pin "2") (pinfunction "2_2") (pintype "passive"))
      (node (ref "SX1") (pin "5") (pinfunction "5_5") (pintype "passive"))
      (node (ref "SX3") (pin "5") (pinfunction "5_5") (pintype "passive"))
    )
    (net (code "10") (name "66.3VAC{slash}ORG{slash}2") (class "Default")
      (node (ref "J4") (pin "6") (pinfunction "6_6") (pintype "bidirectional"))
      (node (ref "R2P") (pin "2") (pinfunction "2_2") (pintype "passive"))
      (node (ref "SX2") (pin "5") (pinfunction "5_5") (pintype "passive"))
      (node (ref "SX4") (pin "5") (pinfunction "5_5") (pintype "passive"))
    )
    (net (code "11") (name "115_VAC_BLK{slash}1") (class "Default")
      (node (ref "D11") (pin "1") (pinfunction "K_1") (pintype "bidirectional"))
      (node (ref "D14") (pin "2") (pinfunction "A_2") (pintype "bidirectional"))
      (node (ref "J1") (pin "2") (pinfunction "2_2") (pintype "bidirectional"))
    )
    (net (code "12") (name "115_VAC_BLK{slash}2") (class "Default")
      (node (ref "D10") (pin "2") (pinfunction "A_2") (pintype "bidirectional"))
      (node (ref "D7") (pin "1") (pinfunction "K_1") (pintype "bidirectional"))
      (node (ref "J4") (pin "2") (pinfunction "2_2") (pintype "bidirectional"))
    )
    (net (code "13") (name "115_VAC_RED{slash}1") (class "Default")
      (node (ref "D12") (pin "1") (pinfunction "K_1") (pintype "bidirectional"))
      (node (ref "D13") (pin "2") (pinfunction "A_2") (pintype "bidirectional"))
      (node (ref "J1") (pin "3") (pinfunction "3_3") (pintype "bidirectional"))
    )
    (net (code "14") (name "115_VAC_RED{slash}2") (class "Default")
      (node (ref "D8") (pin "1") (pinfunction "K_1") (pintype "bidirectional"))
      (node (ref "D9") (pin "2") (pinfunction "A_2") (pintype "bidirectional"))
      (node (ref "J4") (pin "3") (pinfunction "3_3") (pintype "bidirectional"))
    )
    (net (code "15") (name "AGND{slash}1") (class "Default")
      (node (ref "C1") (pin "2") (pinfunction "2_2") (pintype "passive"))
      (node (ref "C3") (pin "2") (pinfunction "2_2") (pintype "passive"))
      (node (ref "J13") (pin "2") (pinfunction "2_2") (pintype "passive"))
      (node (ref "J13") (pin "5") (pinfunction "5_5") (pintype "passive"))
      (node (ref "J3") (pin "1") (pinfunction "SLEEVE_1") (pintype "bidirectional"))
      (node (ref "R10") (pin "1") (pinfunction "1_1") (pintype "passive"))
      (node (ref "R11O") (pin "2") (pinfunction "2_2") (pintype "passive"))
      (node (ref "R19O") (pin "1") (pinfunction "1_1") (pintype "passive"))
      (node (ref "R20O") (pin "2") (pinfunction "2_2") (pintype "passive"))
      (node (ref "R20O1") (pin "1") (pinfunction "1_1") (pintype "passive"))
      (node (ref "R21O") (pin "1") (pinfunction "1_1") (pintype "passive"))
      (node (ref "R3O") (pin "2") (pinfunction "2_2") (pintype "passive"))
      (node (ref "R9") (pin "1") (pinfunction "1_1") (pintype "passive"))
      (node (ref "SH1") (pin "2") (pinfunction "P$2_2") (pintype "bidirectional"))
      (node (ref "U1") (pin "1") (pinfunction "ADJ_1") (pintype "input"))
      (node (ref "Z1") (pin "1") (pinfunction "C_1") (pintype "passive"))
    )
    (net (code "16") (name "AGND{slash}2") (class "Default")
      (node (ref "C2") (pin "2") (pinfunction "2_2") (pintype "passive"))
      (node (ref "C4") (pin "2") (pinfunction "2_2") (pintype "passive"))
      (node (ref "J2") (pin "2") (pinfunction "2_2") (pintype "passive"))
      (node (ref "J2") (pin "5") (pinfunction "5_5") (pintype "passive"))
      (node (ref "R15") (pin "1") (pinfunction "1_1") (pintype "passive"))
      (node (ref "R16") (pin "1") (pinfunction "1_1") (pintype "passive"))
      (node (ref "R20O2") (pin "1") (pinfunction "1_1") (pintype "passive"))
      (node (ref "R22O") (pin "2") (pinfunction "2_2") (pintype "passive"))
      (node (ref "R28O") (pin "1") (pinfunction "1_1") (pintype "passive"))
      (node (ref "R29O") (pin "2") (pinfunction "2_2") (pintype "passive"))
      (node (ref "R30O") (pin "1") (pinfunction "1_1") (pintype "passive"))
      (node (ref "R3O1") (pin "2") (pinfunction "2_2") (pintype "passive"))
      (node (ref "SH2") (pin "2") (pinfunction "P$2_2") (pintype "bidirectional"))
      (node (ref "U2") (pin "1") (pinfunction "ADJ_1") (pintype "input"))
      (node (ref "Z6") (pin "1") (pinfunction "C_1") (pintype "passive"))
    )
    (net (code "17") (name "DGND{slash}1") (class "Default")
      (node (ref "C1P1") (pin "2") (pinfunction "-_2") (pintype "bidirectional"))
      (node (ref "C2P1") (pin "2") (pinfunction "-_2") (pintype "bidirectional"))
      (node (ref "C3P1") (pin "2") (pinfunction "-_2") (pintype "bidirectional"))
      (node (ref "C4P1") (pin "2") (pinfunction "-_2") (pintype "bidirectional"))
      (node (ref "C5P1") (pin "2") (pinfunction "-_2") (pintype "bidirectional"))
      (node (ref "C6P1") (pin "2") (pinfunction "-_2") (pintype "bidirectional"))
      (node (ref "C7P1") (pin "2") (pinfunction "-_2") (pintype "bidirectional"))
      (node (ref "D11") (pin "2") (pinfunction "A_2") (pintype "bidirectional"))
      (node (ref "D12") (pin "2") (pinfunction "A_2") (pintype "bidirectional"))
      (node (ref "R5P1") (pin "1") (pinfunction "1_1") (pintype "passive"))
      (node (ref "SH1") (pin "1") (pinfunction "P$1_1") (pintype "bidirectional"))
    )
    (net (code "18") (name "DGND{slash}2") (class "Default")
      (node (ref "C1P") (pin "2") (pinfunction "-_2") (pintype "bidirectional"))
      (node (ref "C2P") (pin "2") (pinfunction "-_2") (pintype "bidirectional"))
      (node (ref "C3P") (pin "2") (pinfunction "-_2") (pintype "bidirectional"))
      (node (ref "C4P") (pin "2") (pinfunction "-_2") (pintype "bidirectional"))
      (node (ref "C5P") (pin "2") (pinfunction "-_2") (pintype "bidirectional"))
      (node (ref "C6P") (pin "2") (pinfunction "-_2") (pintype "bidirectional"))
      (node (ref "C7P") (pin "2") (pinfunction "-_2") (pintype "bidirectional"))
      (node (ref "D7") (pin "2") (pinfunction "A_2") (pintype "bidirectional"))
      (node (ref "D8") (pin "2") (pinfunction "A_2") (pintype "bidirectional"))
      (node (ref "R5P") (pin "1") (pinfunction "1_1") (pintype "passive"))
      (node (ref "SH2") (pin "1") (pinfunction "P$1_1") (pintype "bidirectional"))
    )
    (net (code "19") (name "L+") (class "Default")
      (node (ref "R23O") (pin "1") (pinfunction "1_1") (pintype "passive"))
      (node (ref "R24O") (pin "1") (pinfunction "1_1") (pintype "passive"))
      (node (ref "R4") (pin "2") (pinfunction "2_2") (pintype "passive"))
    )
    (net (code "20") (name "L-") (class "Default")
      (node (ref "R25O") (pin "1") (pinfunction "1_1") (pintype "passive"))
      (node (ref "R26O") (pin "1") (pinfunction "1_1") (pintype "passive"))
      (node (ref "R3") (pin "2") (pinfunction "2_2") (pintype "passive"))
    )
    (net (code "21") (name "L_OUT") (class "Default")
      (node (ref "C21O1") (pin "1") (pinfunction "1_1") (pintype "passive"))
      (node (ref "C21O1") (pin "4") (pinfunction "1_4") (pintype "passive"))
      (node (ref "J3") (pin "2") (pinfunction "TIP_2") (pintype "bidirectional"))
      (node (ref "R20O2") (pin "2") (pinfunction "2_2") (pintype "passive"))
      (node (ref "Z5") (pin "1") (pinfunction "C_1") (pintype "passive"))
    )
    (net (code "22") (name "Net-(C1P-+)") (class "Default")
      (node (ref "C1P") (pin "1") (pinfunction "+_1") (pintype "bidirectional"))
      (node (ref "D10") (pin "1") (pinfunction "K_1") (pintype "bidirectional"))
      (node (ref "D9") (pin "1") (pinfunction "K_1") (pintype "bidirectional"))
      (node (ref "J4") (pin "4") (pinfunction "4_4") (pintype "bidirectional"))
    )
    (net (code "23") (name "Net-(C1P1-+)") (class "Default")
      (node (ref "C1P1") (pin "1") (pinfunction "+_1") (pintype "bidirectional"))
      (node (ref "D13") (pin "1") (pinfunction "K_1") (pintype "bidirectional"))
      (node (ref "D14") (pin "1") (pinfunction "K_1") (pintype "bidirectional"))
      (node (ref "J1") (pin "4") (pinfunction "4_4") (pintype "bidirectional"))
    )
    (net (code "24") (name "Net-(C2O-Pad1)") (class "Default")
      (node (ref "C2O") (pin "1") (pinfunction "1_1") (pintype "passive"))
      (node (ref "R17") (pin "2") (pinfunction "2_2") (pintype "passive"))
      (node (ref "SX1") (pin "6") (pinfunction "6_6") (pintype "passive"))
    )
    (net (code "25") (name "Net-(C2O-Pad2)") (class "Default")
      (node (ref "C2O") (pin "2") (pinfunction "2_2") (pintype "passive"))
      (node (ref "R3O") (pin "1") (pinfunction "1_1") (pintype "passive"))
      (node (ref "R8") (pin "2") (pinfunction "2_2") (pintype "passive"))
    )
    (net (code "26") (name "Net-(C2O1-Pad1)") (class "Default")
      (node (ref "C2O1") (pin "1") (pinfunction "1_1") (pintype "passive"))
      (node (ref "R18") (pin "1") (pinfunction "1_1") (pintype "passive"))
      (node (ref "SX2") (pin "6") (pinfunction "6_6") (pintype "passive"))
    )
    (net (code "27") (name "Net-(C2O1-Pad2)") (class "Default")
      (node (ref "C2O1") (pin "2") (pinfunction "2_2") (pintype "passive"))
      (node (ref "R14") (pin "2") (pinfunction "2_2") (pintype "passive"))
      (node (ref "R3O1") (pin "1") (pinfunction "1_1") (pintype "passive"))
    )
    (net (code "28") (name "Net-(C2P-+)") (class "Default")
      (node (ref "C2P") (pin "1") (pinfunction "+_1") (pintype "bidirectional"))
      (node (ref "J4") (pin "5") (pinfunction "5_5") (pintype "bidirectional"))
      (node (ref "R6P") (pin "2") (pinfunction "2_2") (pintype "passive"))
    )
    (net (code "29") (name "Net-(C2P1-+)") (class "Default")
      (node (ref "C2P1") (pin "1") (pinfunction "+_1") (pintype "bidirectional"))
      (node (ref "J1") (pin "5") (pinfunction "5_5") (pintype "bidirectional"))
      (node (ref "R6P1") (pin "2") (pinfunction "2_2") (pintype "passive"))
    )
    (net (code "30") (name "Net-(C4P-+)") (class "Default")
      (node (ref "C4P") (pin "1") (pinfunction "+_1") (pintype "bidirectional"))
      (node (ref "R2P") (pin "1") (pinfunction "1_1") (pintype "passive"))
      (node (ref "R3P") (pin "2") (pinfunction "2_2") (pintype "passive"))
      (node (ref "R4P") (pin "1") (pinfunction "1_1") (pintype "passive"))
      (node (ref "R5P") (pin "2") (pinfunction "2_2") (pintype "passive"))
    )
    (net (code "31") (name "Net-(C4P1-+)") (class "Default")
      (node (ref "C4P1") (pin "1") (pinfunction "+_1") (pintype "bidirectional"))
      (node (ref "R2P1") (pin "1") (pinfunction "1_1") (pintype "passive"))
      (node (ref "R3P1") (pin "2") (pinfunction "2_2") (pintype "passive"))
      (node (ref "R4P1") (pin "1") (pinfunction "1_1") (pintype "passive"))
      (node (ref "R5P1") (pin "2") (pinfunction "2_2") (pintype "passive"))
    )
    (net (code "32") (name "Net-(C11O-+)") (class "Default")
      (node (ref "C11O") (pin "1") (pinfunction "+_1") (pintype "passive"))
      (node (ref "J13") (pin "6") (pinfunction "6_6") (pintype "passive"))
    )
    (net (code "33") (name "Net-(C11O--)") (class "Default")
      (node (ref "C11O") (pin "2") (pinfunction "-_2") (pintype "passive"))
      (node (ref "R12O") (pin "2") (pinfunction "2_2") (pintype "passive"))
      (node (ref "R19O") (pin "2") (pinfunction "2_2") (pintype "passive"))
    )
    (net (code "34") (name "Net-(C12O-+)") (class "Default")
      (node (ref "C12O") (pin "1") (pinfunction "+_1") (pintype "passive"))
      (node (ref "J13") (pin "1") (pinfunction "1_1") (pintype "passive"))
    )
    (net (code "35") (name "Net-(C12O--)") (class "Default")
      (node (ref "C12O") (pin "2") (pinfunction "-_2") (pintype "passive"))
      (node (ref "R18O") (pin "2") (pinfunction "2_2") (pintype "passive"))
      (node (ref "R20O") (pin "1") (pinfunction "1_1") (pintype "passive"))
    )
    (net (code "36") (name "Net-(C13O-+)") (class "Default")
      (node (ref "C13O") (pin "1") (pinfunction "+_1") (pintype "passive"))
      (node (ref "J13") (pin "4") (pinfunction "4_4") (pintype "passive"))
    )
    (net (code "37") (name "Net-(C13O--)") (class "Default")
      (node (ref "C13O") (pin "2") (pinfunction "-_2") (pintype "passive"))
      (node (ref "R14O") (pin "2") (pinfunction "2_2") (pintype "passive"))
      (node (ref "R21O") (pin "2") (pinfunction "2_2") (pintype "passive"))
    )
    (net (code "38") (name "Net-(C14O-+)") (class "Default")
      (node (ref "C14O") (pin "1") (pinfunction "+_1") (pintype "passive"))
      (node (ref "J13") (pin "3") (pinfunction "3_3") (pintype "passive"))
    )
    (net (code "39") (name "Net-(C14O--)") (class "Default")
      (node (ref "C14O") (pin "2") (pinfunction "-_2") (pintype "passive"))
      (node (ref "R11O") (pin "1") (pinfunction "1_1") (pintype "passive"))
      (node (ref "R16O") (pin "2") (pinfunction "2_2") (pintype "passive"))
    )
    (net (code "40") (name "Net-(C15O-+)") (class "Default")
      (node (ref "C15O") (pin "1") (pinfunction "+_1") (pintype "passive"))
      (node (ref "J2") (pin "6") (pinfunction "6_6") (pintype "passive"))
    )
    (net (code "41") (name "Net-(C15O--)") (class "Default")
      (node (ref "C15O") (pin "2") (pinfunction "-_2") (pintype "passive"))
      (node (ref "R24O") (pin "2") (pinfunction "2_2") (pintype "passive"))
      (node (ref "R28O") (pin "2") (pinfunction "2_2") (pintype "passive"))
    )
    (net (code "42") (name "Net-(C24O-+)") (class "Default")
      (node (ref "C24O") (pin "1") (pinfunction "+_1") (pintype "passive"))
      (node (ref "J2") (pin "1") (pinfunction "1_1") (pintype "passive"))
    )
    (net (code "43") (name "Net-(C24O--)") (class "Default")
      (node (ref "C24O") (pin "2") (pinfunction "-_2") (pintype "passive"))
      (node (ref "R23O") (pin "2") (pinfunction "2_2") (pintype "passive"))
      (node (ref "R29O") (pin "1") (pinfunction "1_1") (pintype "passive"))
    )
    (net (code "44") (name "Net-(C25O-+)") (class "Default")
      (node (ref "C25O") (pin "1") (pinfunction "+_1") (pintype "passive"))
      (node (ref "J2") (pin "4") (pinfunction "4_4") (pintype "passive"))
    )
    (net (code "45") (name "Net-(C25O--)") (class "Default")
      (node (ref "C25O") (pin "2") (pinfunction "-_2") (pintype "passive"))
      (node (ref "R25O") (pin "2") (pinfunction "2_2") (pintype "passive"))
      (node (ref "R30O") (pin "2") (pinfunction "2_2") (pintype "passive"))
    )
    (net (code "46") (name "Net-(C26O-+)") (class "Default")
      (node (ref "C26O") (pin "1") (pinfunction "+_1") (pintype "passive"))
      (node (ref "J2") (pin "3") (pinfunction "3_3") (pintype "passive"))
    )
    (net (code "47") (name "Net-(C26O--)") (class "Default")
      (node (ref "C26O") (pin "2") (pinfunction "-_2") (pintype "passive"))
      (node (ref "R22O") (pin "1") (pinfunction "1_1") (pintype "passive"))
      (node (ref "R26O") (pin "2") (pinfunction "2_2") (pintype "passive"))
    )
    (net (code "48") (name "Net-(D1-A)") (class "Default")
      (node (ref "D1") (pin "2") (pinfunction "A_2") (pintype "passive"))
      (node (ref "R1") (pin "1") (pinfunction "1_1") (pintype "passive"))
      (node (ref "SX3") (pin "2") (pinfunction "2_2") (pintype "passive"))
    )
    (net (code "49") (name "Net-(D1-C)") (class "Default")
      (node (ref "D1") (pin "1") (pinfunction "C_1") (pintype "passive"))
      (node (ref "D2") (pin "1") (pinfunction "C_1") (pintype "passive"))
      (node (ref "SX3") (pin "3") (pinfunction "3_3") (pintype "passive"))
      (node (ref "SX3") (pin "8") (pinfunction "8_8") (pintype "passive"))
      (node (ref "U1") (pin "3") (pinfunction "IN_3") (pintype "input"))
    )
    (net (code "50") (name "Net-(D2-A)") (class "Default")
      (node (ref "D2") (pin "2") (pinfunction "A_2") (pintype "passive"))
      (node (ref "R2") (pin "1") (pinfunction "1_1") (pintype "passive"))
      (node (ref "SX3") (pin "7") (pinfunction "7_7") (pintype "passive"))
    )
    (net (code "51") (name "Net-(D3-A)") (class "Default")
      (node (ref "D3") (pin "2") (pinfunction "A_2") (pintype "passive"))
      (node (ref "R7") (pin "1") (pinfunction "1_1") (pintype "passive"))
      (node (ref "SX1") (pin "7") (pinfunction "7_7") (pintype "passive"))
    )
    (net (code "52") (name "Net-(D3-C)") (class "Default")
      (node (ref "C21O") (pin "2") (pinfunction "2_2") (pintype "passive"))
      (node (ref "C21O") (pin "3") (pinfunction "2_3") (pintype "passive"))
      (node (ref "D3") (pin "1") (pinfunction "C_1") (pintype "passive"))
      (node (ref "SX1") (pin "1") (pinfunction "1_1") (pintype "passive"))
      (node (ref "SX1") (pin "8") (pinfunction "8_8") (pintype "passive"))
    )
    (net (code "53") (name "Net-(D4-A)") (class "Default")
      (node (ref "D4") (pin "2") (pinfunction "A_2") (pintype "passive"))
      (node (ref "R3") (pin "1") (pinfunction "1_1") (pintype "passive"))
      (node (ref "SX4") (pin "2") (pinfunction "2_2") (pintype "passive"))
    )
    (net (code "54") (name "Net-(D4-C)") (class "Default")
      (node (ref "D4") (pin "1") (pinfunction "C_1") (pintype "passive"))
      (node (ref "D5") (pin "1") (pinfunction "C_1") (pintype "passive"))
      (node (ref "SX4") (pin "3") (pinfunction "3_3") (pintype "passive"))
      (node (ref "SX4") (pin "8") (pinfunction "8_8") (pintype "passive"))
      (node (ref "U2") (pin "3") (pinfunction "IN_3") (pintype "input"))
    )
    (net (code "55") (name "Net-(D5-A)") (class "Default")
      (node (ref "D5") (pin "2") (pinfunction "A_2") (pintype "passive"))
      (node (ref "R4") (pin "1") (pinfunction "1_1") (pintype "passive"))
      (node (ref "SX4") (pin "7") (pinfunction "7_7") (pintype "passive"))
    )
    (net (code "56") (name "Net-(D6-A)") (class "Default")
      (node (ref "D6") (pin "2") (pinfunction "A_2") (pintype "passive"))
      (node (ref "R13") (pin "1") (pinfunction "1_1") (pintype "passive"))
      (node (ref "SX2") (pin "7") (pinfunction "7_7") (pintype "passive"))
    )
    (net (code "57") (name "Net-(D6-C)") (class "Default")
      (node (ref "C21O1") (pin "2") (pinfunction "2_2") (pintype "passive"))
      (node (ref "C21O1") (pin "3") (pinfunction "2_3") (pintype "passive"))
      (node (ref "D6") (pin "1") (pinfunction "C_1") (pintype "passive"))
      (node (ref "SX2") (pin "1") (pinfunction "1_1") (pintype "passive"))
      (node (ref "SX2") (pin "8") (pinfunction "8_8") (pintype "passive"))
    )
    (net (code "58") (name "Net-(R5-Pad1)") (class "Default")
      (node (ref "R5") (pin "1") (pinfunction "1_1") (pintype "passive"))
      (node (ref "SX3") (pin "1") (pinfunction "1_1") (pintype "passive"))
    )
    (net (code "59") (name "Net-(R11-Pad1)") (class "Default")
      (node (ref "R11") (pin "1") (pinfunction "1_1") (pintype "passive"))
      (node (ref "SX4") (pin "1") (pinfunction "1_1") (pintype "passive"))
    )
    (net (code "60") (name "Net-(R13-Pad2)") (class "Default")
      (node (ref "R13") (pin "2") (pinfunction "2_2") (pintype "passive"))
      (node (ref "R20") (pin "2") (pinfunction "2_2") (pintype "passive"))
      (node (ref "SX4") (pin "6") (pinfunction "6_6") (pintype "passive"))
    )
    (net (code "61") (name "Net-(R19-Pad1)") (class "Default")
      (node (ref "R19") (pin "1") (pinfunction "1_1") (pintype "passive"))
      (node (ref "R7") (pin "2") (pinfunction "2_2") (pintype "passive"))
      (node (ref "SX3") (pin "6") (pinfunction "6_6") (pintype "passive"))
    )
    (net (code "62") (name "Net-(U1-OUT)") (class "Default")
      (node (ref "R10") (pin "2") (pinfunction "2_2") (pintype "passive"))
      (node (ref "U1") (pin "2") (pinfunction "OUT_2") (pintype "passive"))
    )
    (net (code "63") (name "Net-(U2-OUT)") (class "Default")
      (node (ref "R16") (pin "2") (pinfunction "2_2") (pintype "passive"))
      (node (ref "U2") (pin "2") (pinfunction "OUT_2") (pintype "passive"))
    )
    (net (code "64") (name "Net-(Z1-A)") (class "Default")
      (node (ref "Z1") (pin "2") (pinfunction "A_2") (pintype "passive"))
      (node (ref "Z2") (pin "2") (pinfunction "A_2") (pintype "passive"))
    )
    (net (code "65") (name "Net-(Z3-A)") (class "Default")
      (node (ref "R8") (pin "1") (pinfunction "1_1") (pintype "passive"))
      (node (ref "SX1") (pin "2") (pinfunction "2_2") (pintype "passive"))
      (node (ref "Z3") (pin "2") (pinfunction "A_2") (pintype "passive"))
    )
    (net (code "66") (name "Net-(Z3-C)") (class "Default")
      (node (ref "R9") (pin "2") (pinfunction "2_2") (pintype "passive"))
      (node (ref "SX1") (pin "3") (pinfunction "3_3") (pintype "passive"))
      (node (ref "Z3") (pin "1") (pinfunction "C_1") (pintype "passive"))
    )
    (net (code "67") (name "Net-(Z4-A)") (class "Default")
      (node (ref "R14") (pin "1") (pinfunction "1_1") (pintype "passive"))
      (node (ref "SX2") (pin "2") (pinfunction "2_2") (pintype "passive"))
      (node (ref "Z4") (pin "2") (pinfunction "A_2") (pintype "passive"))
    )
    (net (code "68") (name "Net-(Z4-C)") (class "Default")
      (node (ref "R15") (pin "2") (pinfunction "2_2") (pintype "passive"))
      (node (ref "SX2") (pin "3") (pinfunction "3_3") (pintype "passive"))
      (node (ref "Z4") (pin "1") (pinfunction "C_1") (pintype "passive"))
    )
    (net (code "69") (name "Net-(Z5-A)") (class "Default")
      (node (ref "Z5") (pin "2") (pinfunction "A_2") (pintype "passive"))
      (node (ref "Z6") (pin "2") (pinfunction "A_2") (pintype "passive"))
    )
    (net (code "70") (name "PE") (class "Default")
      (node (ref "J1") (pin "1") (pinfunction "1_1") (pintype "bidirectional"))
      (node (ref "J4") (pin "1") (pinfunction "1_1") (pintype "bidirectional"))
    )
    (net (code "71") (name "R+") (class "Default")
      (node (ref "R12O") (pin "1") (pinfunction "1_1") (pintype "passive"))
      (node (ref "R18O") (pin "1") (pinfunction "1_1") (pintype "passive"))
      (node (ref "R2") (pin "2") (pinfunction "2_2") (pintype "passive"))
    )
    (net (code "72") (name "R-") (class "Default")
      (node (ref "R1") (pin "2") (pinfunction "2_2") (pintype "passive"))
      (node (ref "R14O") (pin "1") (pinfunction "1_1") (pintype "passive"))
      (node (ref "R16O") (pin "1") (pinfunction "1_1") (pintype "passive"))
    )
    (net (code "73") (name "R_OUT") (class "Default")
      (node (ref "C21O") (pin "1") (pinfunction "1_1") (pintype "passive"))
      (node (ref "C21O") (pin "4") (pinfunction "1_4") (pintype "passive"))
      (node (ref "J3") (pin "3") (pinfunction "RING_3") (pintype "bidirectional"))
      (node (ref "R20O1") (pin "2") (pinfunction "2_2") (pintype "passive"))
      (node (ref "Z2") (pin "1") (pinfunction "C_1") (pintype "passive"))
    )
    (net (code "74") (name "unconnected-(SX1-Pad9)") (class "Default")
      (node (ref "SX1") (pin "9") (pinfunction "9_9") (pintype "passive"))
    )
    (net (code "75") (name "unconnected-(SX2-Pad9)") (class "Default")
      (node (ref "SX2") (pin "9") (pinfunction "9_9") (pintype "passive"))
    )
    (net (code "76") (name "unconnected-(SX3-Pad9)") (class "Default")
      (node (ref "SX3") (pin "9") (pinfunction "9_9") (pintype "passive"))
    )
    (net (code "77") (name "unconnected-(SX4-Pad9)") (class "Default")
      (node (ref "SX4") (pin "9") (pinfunction "9_9") (pintype "passive"))
    )
  )
)
